# Temp.net
KiCad netlist of a schematic drawn in EAGLE
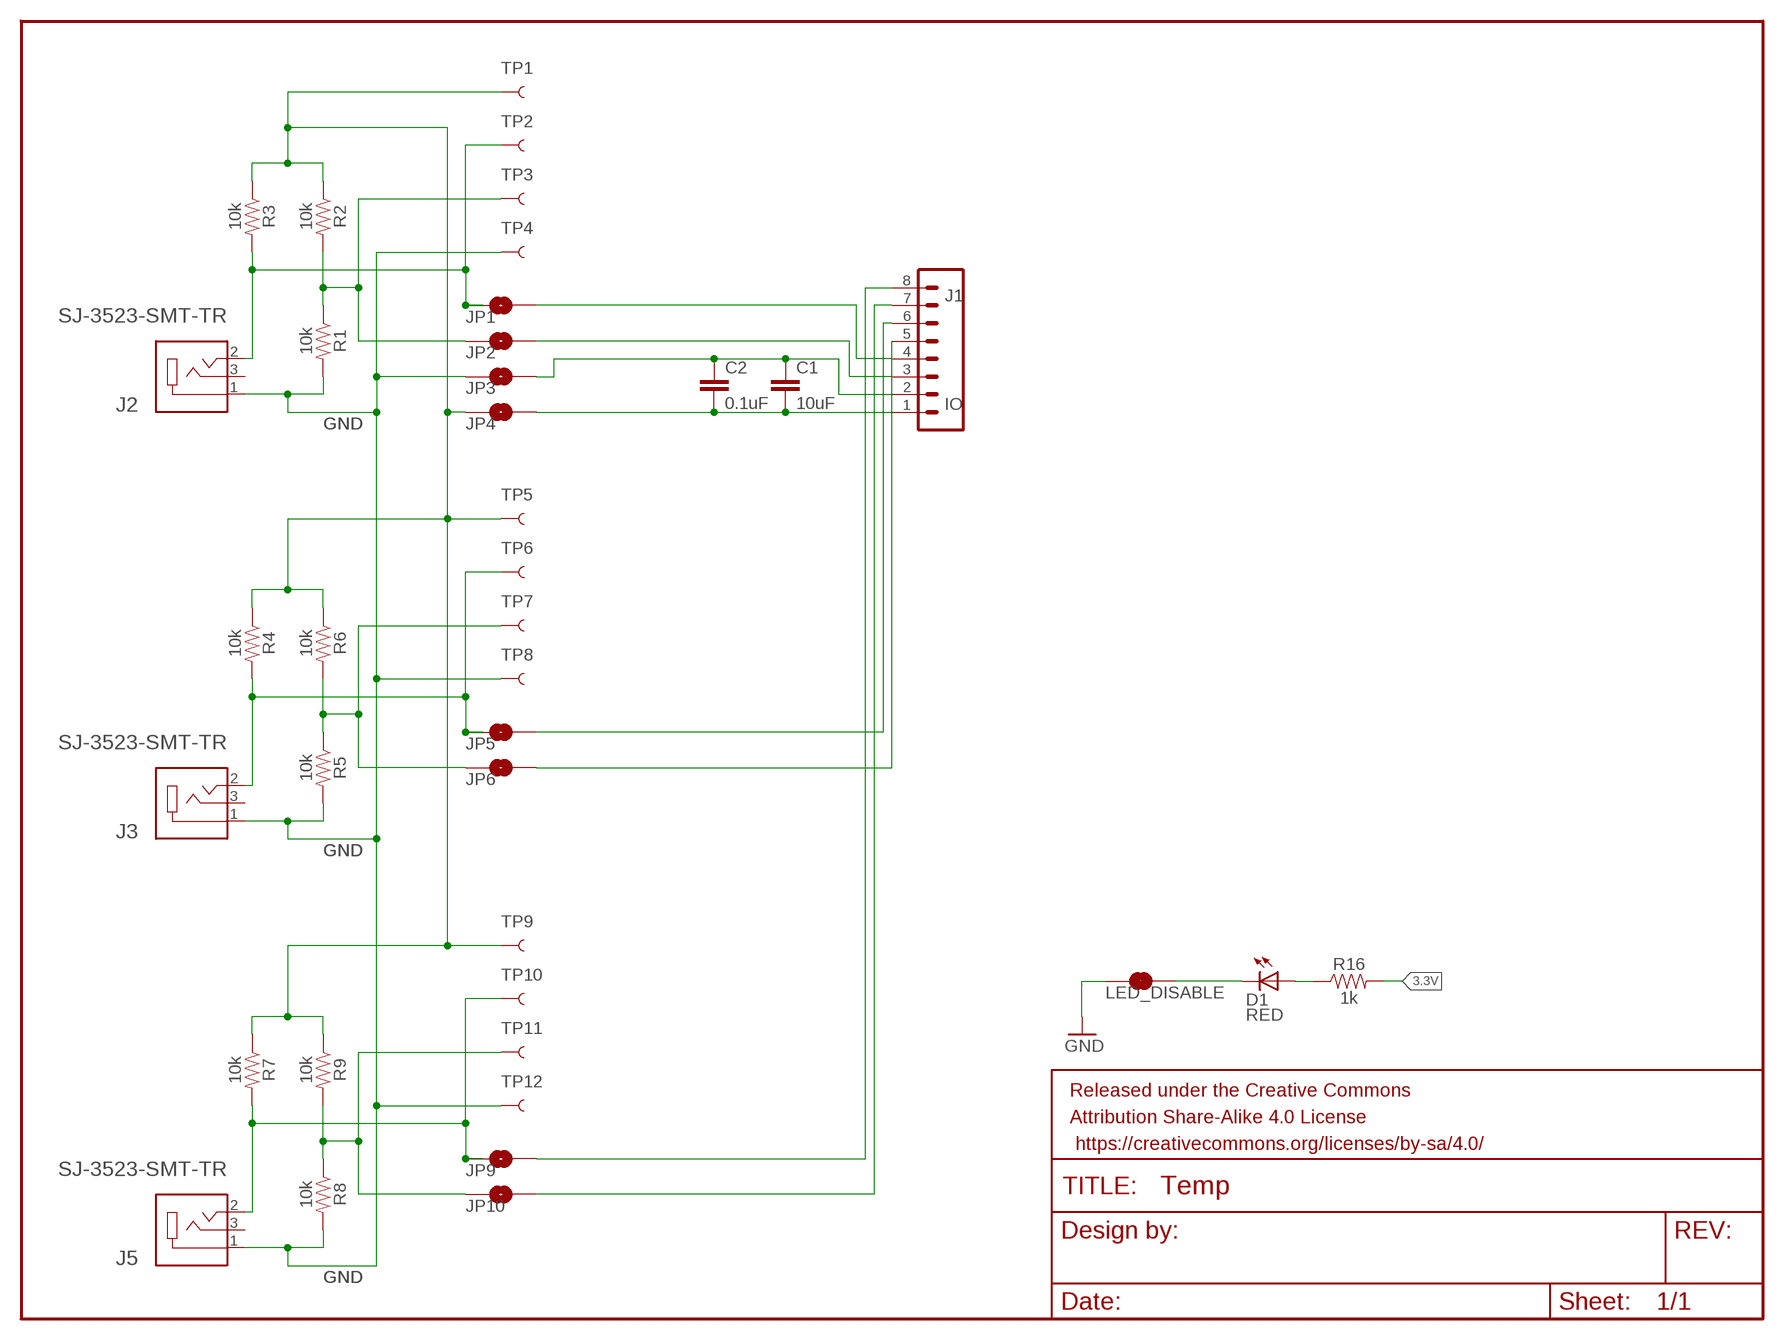
[diagram p0: schematic, sheet 1]

(export (version "E")
  (design (tool "Eeschema 10.0.6"))
  (components
    (comp (ref "C1")
      (value "10uF")
      (footprint "eagle-import:0603")
      (libsource (lib "eagle-import") (part "10UF-0603-6.3V-20%"))
    )
    (comp (ref "C2")
      (value "0.1uF")
      (footprint "eagle-import:0603")
      (libsource (lib "eagle-import") (part "0.1UF-0603-25V-(+80/-20%)"))
    )
    (comp (ref "D1")
      (value "RED")
      (footprint "eagle-import:LED-0603")
      (libsource (lib "eagle-import") (part "LED-RED0603"))
    )
    (comp (ref "FRAME1")
      (value "FRAME-LETTERNO_PACKAGE")
      (footprint "eagle-import:DUMMY")
      (fields (field (name "DESIGNER") "Nobody"))
      (libsource (lib "eagle-import") (part "FRAME-LETTERNO_PACKAGE"))
    )
    (comp (ref "J1")
      (value "IO")
      (footprint "eagle-import:1X08")
      (libsource (lib "eagle-import") (part "CONN_08{dblquote}"))
    )
    (comp (ref "J2")
      (value "SJ-3523-SMT-TR")
      (footprint "eagle-import:CUI_SJ-3523-SMT-TR")
      (fields (field (name "MF") "CUI Devices"))
      (libsource (lib "eagle-import") (part "SJ-3523-SMT-TR"))
    )
    (comp (ref "J3")
      (value "SJ-3523-SMT-TR")
      (footprint "eagle-import:CUI_SJ-3523-SMT-TR")
      (fields (field (name "MF") "CUI Devices"))
      (libsource (lib "eagle-import") (part "SJ-3523-SMT-TR"))
    )
    (comp (ref "J5")
      (value "SJ-3523-SMT-TR")
      (footprint "eagle-import:CUI_SJ-3523-SMT-TR")
      (fields (field (name "MF") "CUI Devices"))
      (libsource (lib "eagle-import") (part "SJ-3523-SMT-TR"))
    )
    (comp (ref "JP1")
      (value "JUMPER-SMT_2_NO_NO-SILK")
      (footprint "eagle-import:SMT-JUMPER_2_NO_NO-SILK")
      (libsource (lib "eagle-import") (part "JUMPER-SMT_2_NO_NO-SILK"))
    )
    (comp (ref "JP2")
      (value "JUMPER-SMT_2_NO_NO-SILK")
      (footprint "eagle-import:SMT-JUMPER_2_NO_NO-SILK")
      (libsource (lib "eagle-import") (part "JUMPER-SMT_2_NO_NO-SILK"))
    )
    (comp (ref "JP3")
      (value "JUMPER-SMT_2_NO_NO-SILK")
      (footprint "eagle-import:SMT-JUMPER_2_NO_NO-SILK")
      (libsource (lib "eagle-import") (part "JUMPER-SMT_2_NO_NO-SILK"))
    )
    (comp (ref "JP4")
      (value "JUMPER-SMT_2_NO_NO-SILK")
      (footprint "eagle-import:SMT-JUMPER_2_NO_NO-SILK")
      (libsource (lib "eagle-import") (part "JUMPER-SMT_2_NO_NO-SILK"))
    )
    (comp (ref "JP5")
      (value "JUMPER-SMT_2_NO_NO-SILK")
      (footprint "eagle-import:SMT-JUMPER_2_NO_NO-SILK")
      (libsource (lib "eagle-import") (part "JUMPER-SMT_2_NO_NO-SILK"))
    )
    (comp (ref "JP6")
      (value "JUMPER-SMT_2_NO_NO-SILK")
      (footprint "eagle-import:SMT-JUMPER_2_NO_NO-SILK")
      (libsource (lib "eagle-import") (part "JUMPER-SMT_2_NO_NO-SILK"))
    )
    (comp (ref "JP9")
      (value "JUMPER-SMT_2_NO_NO-SILK")
      (footprint "eagle-import:SMT-JUMPER_2_NO_NO-SILK")
      (libsource (lib "eagle-import") (part "JUMPER-SMT_2_NO_NO-SILK"))
    )
    (comp (ref "JP10")
      (value "JUMPER-SMT_2_NO_NO-SILK")
      (footprint "eagle-import:SMT-JUMPER_2_NO_NO-SILK")
      (libsource (lib "eagle-import") (part "JUMPER-SMT_2_NO_NO-SILK"))
    )
    (comp (ref "LED_DISABLE")
      (value "JUMPER-SMT_2_NC_TRACE_SILK")
      (footprint "eagle-import:SMT-JUMPER_2_NC_TRACE_SILK")
      (libsource (lib "eagle-import") (part "JUMPER-SMT_2_NC_TRACE_SILK"))
    )
    (comp (ref "R1")
      (value "10k")
      (footprint "eagle-import:0603")
      (libsource (lib "eagle-import") (part "10KOHM-0603-1/10W-1%"))
    )
    (comp (ref "R2")
      (value "10k")
      (footprint "eagle-import:0603")
      (libsource (lib "eagle-import") (part "10KOHM-0603-1/10W-1%"))
    )
    (comp (ref "R3")
      (value "10k")
      (footprint "eagle-import:0603")
      (libsource (lib "eagle-import") (part "10KOHM-0603-1/10W-1%"))
    )
    (comp (ref "R4")
      (value "10k")
      (footprint "eagle-import:0603")
      (libsource (lib "eagle-import") (part "10KOHM-0603-1/10W-1%"))
    )
    (comp (ref "R5")
      (value "10k")
      (footprint "eagle-import:0603")
      (libsource (lib "eagle-import") (part "10KOHM-0603-1/10W-1%"))
    )
    (comp (ref "R6")
      (value "10k")
      (footprint "eagle-import:0603")
      (libsource (lib "eagle-import") (part "10KOHM-0603-1/10W-1%"))
    )
    (comp (ref "R7")
      (value "10k")
      (footprint "eagle-import:0603")
      (libsource (lib "eagle-import") (part "10KOHM-0603-1/10W-1%"))
    )
    (comp (ref "R8")
      (value "10k")
      (footprint "eagle-import:0603")
      (libsource (lib "eagle-import") (part "10KOHM-0603-1/10W-1%"))
    )
    (comp (ref "R9")
      (value "10k")
      (footprint "eagle-import:0603")
      (libsource (lib "eagle-import") (part "10KOHM-0603-1/10W-1%"))
    )
    (comp (ref "R16")
      (value "1k")
      (footprint "eagle-import:0603")
      (libsource (lib "eagle-import") (part "1KOHM-0603-1/10W-1%"))
    )
    (comp (ref "TP1")
      (value "TEST-POINT3X5")
      (footprint "eagle-import:PAD.03X.05")
      (libsource (lib "eagle-import") (part "TEST-POINT3X5"))
    )
    (comp (ref "TP2")
      (value "TEST-POINT3X5")
      (footprint "eagle-import:PAD.03X.05")
      (libsource (lib "eagle-import") (part "TEST-POINT3X5"))
    )
    (comp (ref "TP3")
      (value "TEST-POINT3X5")
      (footprint "eagle-import:PAD.03X.05")
      (libsource (lib "eagle-import") (part "TEST-POINT3X5"))
    )
    (comp (ref "TP4")
      (value "TEST-POINT3X5")
      (footprint "eagle-import:PAD.03X.05")
      (libsource (lib "eagle-import") (part "TEST-POINT3X5"))
    )
    (comp (ref "TP5")
      (value "TEST-POINT3X5")
      (footprint "eagle-import:PAD.03X.05")
      (libsource (lib "eagle-import") (part "TEST-POINT3X5"))
    )
    (comp (ref "TP6")
      (value "TEST-POINT3X5")
      (footprint "eagle-import:PAD.03X.05")
      (libsource (lib "eagle-import") (part "TEST-POINT3X5"))
    )
    (comp (ref "TP7")
      (value "TEST-POINT3X5")
      (footprint "eagle-import:PAD.03X.05")
      (libsource (lib "eagle-import") (part "TEST-POINT3X5"))
    )
    (comp (ref "TP8")
      (value "TEST-POINT3X5")
      (footprint "eagle-import:PAD.03X.05")
      (libsource (lib "eagle-import") (part "TEST-POINT3X5"))
    )
    (comp (ref "TP9")
      (value "TEST-POINT3X5")
      (footprint "eagle-import:PAD.03X.05")
      (libsource (lib "eagle-import") (part "TEST-POINT3X5"))
    )
    (comp (ref "TP10")
      (value "TEST-POINT3X5")
      (footprint "eagle-import:PAD.03X.05")
      (libsource (lib "eagle-import") (part "TEST-POINT3X5"))
    )
    (comp (ref "TP11")
      (value "TEST-POINT3X5")
      (footprint "eagle-import:PAD.03X.05")
      (libsource (lib "eagle-import") (part "TEST-POINT3X5"))
    )
    (comp (ref "TP12")
      (value "TEST-POINT3X5")
      (footprint "eagle-import:PAD.03X.05")
      (libsource (lib "eagle-import") (part "TEST-POINT3X5"))
    )
  )
  (nets
    (net (code "1") (name "3.3V") (class "Default")
      (node (ref "JP4") (pin "1") (pinfunction "1_1") (pintype "passive"))
      (node (ref "R16") (pin "2") (pinfunction "2_2") (pintype "passive"))
      (node (ref "R2") (pin "1") (pinfunction "1_1") (pintype "passive"))
      (node (ref "R3") (pin "1") (pinfunction "1_1") (pintype "passive"))
      (node (ref "R4") (pin "1") (pinfunction "1_1") (pintype "passive"))
      (node (ref "R6") (pin "1") (pinfunction "1_1") (pintype "passive"))
      (node (ref "R7") (pin "1") (pinfunction "1_1") (pintype "passive"))
      (node (ref "R9") (pin "1") (pinfunction "1_1") (pintype "passive"))
      (node (ref "TP1") (pin "P$1") (pinfunction "1_P$1") (pintype "bidirectional"))
      (node (ref "TP5") (pin "P$1") (pinfunction "1_P$1") (pintype "bidirectional"))
      (node (ref "TP9") (pin "P$1") (pinfunction "1_P$1") (pintype "bidirectional"))
    )
    (net (code "2") (name "GND") (class "Default")
      (node (ref "J2") (pin "1") (pinfunction "1_1") (pintype "passive"))
      (node (ref "J3") (pin "1") (pinfunction "1_1") (pintype "passive"))
      (node (ref "J5") (pin "1") (pinfunction "1_1") (pintype "passive"))
      (node (ref "JP3") (pin "1") (pinfunction "1_1") (pintype "passive"))
      (node (ref "LED_DISABLE") (pin "1") (pinfunction "1_1") (pintype "passive"))
      (node (ref "R1") (pin "2") (pinfunction "2_2") (pintype "passive"))
      (node (ref "R5") (pin "2") (pinfunction "2_2") (pintype "passive"))
      (node (ref "R8") (pin "2") (pinfunction "2_2") (pintype "passive"))
      (node (ref "TP12") (pin "P$1") (pinfunction "1_P$1") (pintype "bidirectional"))
      (node (ref "TP4") (pin "P$1") (pinfunction "1_P$1") (pintype "bidirectional"))
      (node (ref "TP8") (pin "P$1") (pinfunction "1_P$1") (pintype "bidirectional"))
    )
    (net (code "3") (name "Net-(C1-Pad1)") (class "Default")
      (node (ref "C1") (pin "1") (pinfunction "1_1") (pintype "passive"))
      (node (ref "C2") (pin "1") (pinfunction "1_1") (pintype "passive"))
      (node (ref "J1") (pin "2") (pinfunction "2_2") (pintype "passive"))
      (node (ref "JP3") (pin "2") (pinfunction "2_2") (pintype "passive"))
    )
    (net (code "4") (name "Net-(C1-Pad2)") (class "Default")
      (node (ref "C1") (pin "2") (pinfunction "2_2") (pintype "passive"))
      (node (ref "C2") (pin "2") (pinfunction "2_2") (pintype "passive"))
      (node (ref "J1") (pin "1") (pinfunction "1_1") (pintype "passive"))
      (node (ref "JP4") (pin "2") (pinfunction "2_2") (pintype "passive"))
    )
    (net (code "5") (name "Net-(D1-PadA)") (class "Default")
      (node (ref "D1") (pin "A") (pinfunction "A_A") (pintype "passive"))
      (node (ref "R16") (pin "1") (pinfunction "1_1") (pintype "passive"))
    )
    (net (code "6") (name "Net-(D1-PadC)") (class "Default")
      (node (ref "D1") (pin "C") (pinfunction "C_C") (pintype "passive"))
      (node (ref "LED_DISABLE") (pin "2") (pinfunction "2_2") (pintype "passive"))
    )
    (net (code "7") (name "Net-(J1-Pad3)") (class "Default")
      (node (ref "J1") (pin "3") (pinfunction "3_3") (pintype "passive"))
      (node (ref "JP2") (pin "2") (pinfunction "2_2") (pintype "passive"))
    )
    (net (code "8") (name "Net-(J1-Pad4)") (class "Default")
      (node (ref "J1") (pin "4") (pinfunction "4_4") (pintype "passive"))
      (node (ref "JP1") (pin "2") (pinfunction "2_2") (pintype "passive"))
    )
    (net (code "9") (name "Net-(J1-Pad5)") (class "Default")
      (node (ref "J1") (pin "5") (pinfunction "5_5") (pintype "passive"))
      (node (ref "JP6") (pin "2") (pinfunction "2_2") (pintype "passive"))
    )
    (net (code "10") (name "Net-(J1-Pad6)") (class "Default")
      (node (ref "J1") (pin "6") (pinfunction "6_6") (pintype "passive"))
      (node (ref "JP5") (pin "2") (pinfunction "2_2") (pintype "passive"))
    )
    (net (code "11") (name "Net-(J1-Pad7)") (class "Default")
      (node (ref "J1") (pin "7") (pinfunction "7_7") (pintype "passive"))
      (node (ref "JP10") (pin "2") (pinfunction "2_2") (pintype "passive"))
    )
    (net (code "12") (name "Net-(J1-Pad8)") (class "Default")
      (node (ref "J1") (pin "8") (pinfunction "8_8") (pintype "passive"))
      (node (ref "JP9") (pin "2") (pinfunction "2_2") (pintype "passive"))
    )
    (net (code "13") (name "Net-(TP2-1)") (class "Default")
      (node (ref "J2") (pin "2") (pinfunction "2_2") (pintype "passive"))
      (node (ref "JP1") (pin "1") (pinfunction "1_1") (pintype "passive"))
      (node (ref "R3") (pin "2") (pinfunction "2_2") (pintype "passive"))
      (node (ref "TP2") (pin "P$1") (pinfunction "1_P$1") (pintype "bidirectional"))
    )
    (net (code "14") (name "Net-(TP3-1)") (class "Default")
      (node (ref "JP2") (pin "1") (pinfunction "1_1") (pintype "passive"))
      (node (ref "R1") (pin "1") (pinfunction "1_1") (pintype "passive"))
      (node (ref "R2") (pin "2") (pinfunction "2_2") (pintype "passive"))
      (node (ref "TP3") (pin "P$1") (pinfunction "1_P$1") (pintype "bidirectional"))
    )
    (net (code "15") (name "Net-(TP6-1)") (class "Default")
      (node (ref "J3") (pin "2") (pinfunction "2_2") (pintype "passive"))
      (node (ref "JP5") (pin "1") (pinfunction "1_1") (pintype "passive"))
      (node (ref "R4") (pin "2") (pinfunction "2_2") (pintype "passive"))
      (node (ref "TP6") (pin "P$1") (pinfunction "1_P$1") (pintype "bidirectional"))
    )
    (net (code "16") (name "Net-(TP7-1)") (class "Default")
      (node (ref "JP6") (pin "1") (pinfunction "1_1") (pintype "passive"))
      (node (ref "R5") (pin "1") (pinfunction "1_1") (pintype "passive"))
      (node (ref "R6") (pin "2") (pinfunction "2_2") (pintype "passive"))
      (node (ref "TP7") (pin "P$1") (pinfunction "1_P$1") (pintype "bidirectional"))
    )
    (net (code "17") (name "Net-(TP10-1)") (class "Default")
      (node (ref "J5") (pin "2") (pinfunction "2_2") (pintype "passive"))
      (node (ref "JP9") (pin "1") (pinfunction "1_1") (pintype "passive"))
      (node (ref "R7") (pin "2") (pinfunction "2_2") (pintype "passive"))
      (node (ref "TP10") (pin "P$1") (pinfunction "1_P$1") (pintype "bidirectional"))
    )
    (net (code "18") (name "Net-(TP11-1)") (class "Default")
      (node (ref "JP10") (pin "1") (pinfunction "1_1") (pintype "passive"))
      (node (ref "R8") (pin "1") (pinfunction "1_1") (pintype "passive"))
      (node (ref "R9") (pin "2") (pinfunction "2_2") (pintype "passive"))
      (node (ref "TP11") (pin "P$1") (pinfunction "1_P$1") (pintype "bidirectional"))
    )
    (net (code "19") (name "unconnected-(J2-Pad3)") (class "Default")
      (node (ref "J2") (pin "3") (pinfunction "3_3") (pintype "passive"))
    )
    (net (code "20") (name "unconnected-(J3-Pad3)") (class "Default")
      (node (ref "J3") (pin "3") (pinfunction "3_3") (pintype "passive"))
    )
    (net (code "21") (name "unconnected-(J5-Pad3)") (class "Default")
      (node (ref "J5") (pin "3") (pinfunction "3_3") (pintype "passive"))
    )
  )
)
